# A_INPUT.net
KiCad netlist of a schematic drawn in Altium Designer
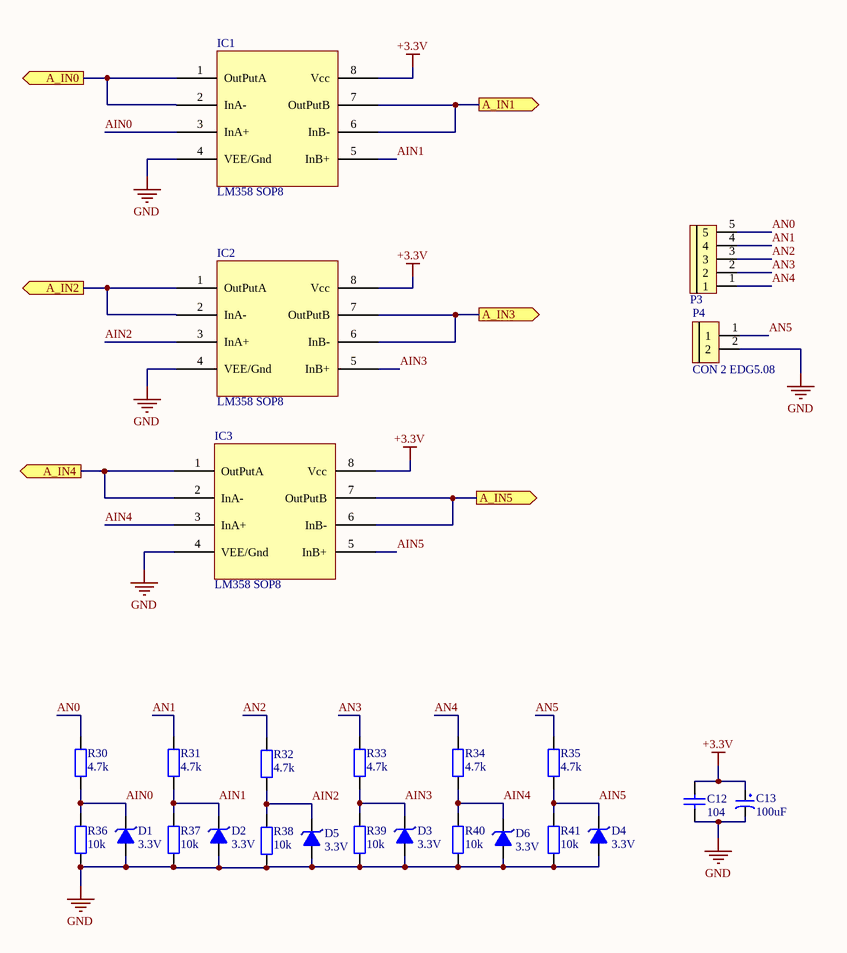
[diagram p0: A_INPUT.SchDoc]

(export (version "E")
  (design (tool "Eeschema 10.0.6"))
  (components
    (comp (ref "C12")
      (value "104")
      (footprint "tu 0805")
      (description "Dán")
      (libsource (lib "Altium_Lib_by_KhueNguyenCreator") (part "Tu 0805 104 50V 10%"))
    )
    (comp (ref "C13")
      (value "100uF")
      (footprint "tu hoa 5mm")
      (description "Cắm")
      (libsource (lib "Altium_Lib_by_KhueNguyenCreator") (part "Tu Hoa 100uF 16V 5x7"))
    )
    (comp (ref "D1")
      (value "3.3V")
      (footprint "DIODE ZENNER SMD SOD80")
      (description "Dán")
      (libsource (lib "Altium_Lib_by_KhueNguyenCreator") (part "Diode Zener 3.3V"))
    )
    (comp (ref "D2")
      (value "3.3V")
      (footprint "DIODE ZENNER SMD SOD80")
      (description "Dán")
      (libsource (lib "Altium_Lib_by_KhueNguyenCreator") (part "Diode Zener 3.3V"))
    )
    (comp (ref "D3")
      (value "3.3V")
      (footprint "DIODE ZENNER SMD SOD80")
      (description "Dán")
      (libsource (lib "Altium_Lib_by_KhueNguyenCreator") (part "Diode Zener 3.3V"))
    )
    (comp (ref "D4")
      (value "3.3V")
      (footprint "DIODE ZENNER SMD SOD80")
      (description "Dán")
      (libsource (lib "Altium_Lib_by_KhueNguyenCreator") (part "Diode Zener 3.3V"))
    )
    (comp (ref "D5")
      (value "3.3V")
      (footprint "DIODE ZENNER SMD SOD80")
      (description "Dán")
      (libsource (lib "Altium_Lib_by_KhueNguyenCreator") (part "Diode Zener 3.3V"))
    )
    (comp (ref "D6")
      (value "3.3V")
      (footprint "DIODE ZENNER SMD SOD80")
      (description "Dán")
      (libsource (lib "Altium_Lib_by_KhueNguyenCreator") (part "Diode Zener 3.3V"))
    )
    (comp (ref "IC1")
      (value "LM358 SOP8")
      (footprint "SOP 8")
      (description "Dán")
      (libsource (lib "Altium_Lib_by_KhueNguyenCreator") (part "LM358 SOP8"))
    )
    (comp (ref "IC2")
      (value "LM358 SOP8")
      (footprint "SOP 8")
      (description "Dán")
      (libsource (lib "Altium_Lib_by_KhueNguyenCreator") (part "LM358 SOP8"))
    )
    (comp (ref "IC3")
      (value "LM358 SOP8")
      (footprint "SOP 8")
      (description "Dán")
      (libsource (lib "Altium_Lib_by_KhueNguyenCreator") (part "LM358 SOP8"))
    )
    (comp (ref "P3")
      (value "CON 5 EDG5.08")
      (footprint "CON 5 5EDG5.08")
      (description "Cắm")
      (libsource (lib "Altium_Lib_by_KhueNguyenCreator") (part "CON 5 EDG5.08"))
    )
    (comp (ref "P4")
      (value "CON 2 EDG5.08")
      (footprint "CON 2 2EDG5.08")
      (description "Cắm")
      (libsource (lib "Altium_Lib_by_KhueNguyenCreator") (part "CON 2 EDG5.08"))
    )
    (comp (ref "R30")
      (value "4.7k")
      (footprint "tro smd 0805")
      (description "Dán")
      (libsource (lib "Altium_Lib_by_KhueNguyenCreator") (part "Tro 0805 1% 5.1k"))
    )
    (comp (ref "R31")
      (value "4.7k")
      (footprint "tro smd 0805")
      (description "Dán")
      (libsource (lib "Altium_Lib_by_KhueNguyenCreator") (part "Tro 0805 1% 5.1k"))
    )
    (comp (ref "R32")
      (value "4.7k")
      (footprint "tro smd 0805")
      (description "Dán")
      (libsource (lib "Altium_Lib_by_KhueNguyenCreator") (part "Tro 0805 1% 5.1k"))
    )
    (comp (ref "R33")
      (value "4.7k")
      (footprint "tro smd 0805")
      (description "Dán")
      (libsource (lib "Altium_Lib_by_KhueNguyenCreator") (part "Tro 0805 1% 5.1k"))
    )
    (comp (ref "R34")
      (value "4.7k")
      (footprint "tro smd 0805")
      (description "Dán")
      (libsource (lib "Altium_Lib_by_KhueNguyenCreator") (part "Tro 0805 1% 5.1k"))
    )
    (comp (ref "R35")
      (value "4.7k")
      (footprint "tro smd 0805")
      (description "Dán")
      (libsource (lib "Altium_Lib_by_KhueNguyenCreator") (part "Tro 0805 1% 5.1k"))
    )
    (comp (ref "R36")
      (value "10k")
      (footprint "tro smd 0805")
      (description "Dán")
      (libsource (lib "Altium_Lib_by_KhueNguyenCreator") (part "Tro 0805 1% 10k"))
    )
    (comp (ref "R37")
      (value "10k")
      (footprint "tro smd 0805")
      (description "Dán")
      (libsource (lib "Altium_Lib_by_KhueNguyenCreator") (part "Tro 0805 1% 10k"))
    )
    (comp (ref "R38")
      (value "10k")
      (footprint "tro smd 0805")
      (description "Dán")
      (libsource (lib "Altium_Lib_by_KhueNguyenCreator") (part "Tro 0805 1% 10k"))
    )
    (comp (ref "R39")
      (value "10k")
      (footprint "tro smd 0805")
      (description "Dán")
      (libsource (lib "Altium_Lib_by_KhueNguyenCreator") (part "Tro 0805 1% 10k"))
    )
    (comp (ref "R40")
      (value "10k")
      (footprint "tro smd 0805")
      (description "Dán")
      (libsource (lib "Altium_Lib_by_KhueNguyenCreator") (part "Tro 0805 1% 10k"))
    )
    (comp (ref "R41")
      (value "10k")
      (footprint "tro smd 0805")
      (description "Dán")
      (libsource (lib "Altium_Lib_by_KhueNguyenCreator") (part "Tro 0805 1% 10k"))
    )
  )
  (nets
    (net (code "1") (name "+3.3V") (class "Default")
      (node (ref "C12") (pin "1") (pinfunction "1_1") (pintype "passive"))
      (node (ref "C13") (pin "1") (pinfunction "1_1") (pintype "passive"))
      (node (ref "IC1") (pin "8") (pinfunction "Vcc_8") (pintype "passive"))
      (node (ref "IC2") (pin "8") (pinfunction "Vcc_8") (pintype "passive"))
      (node (ref "IC3") (pin "8") (pinfunction "Vcc_8") (pintype "passive"))
    )
    (net (code "2") (name "/AIN0") (class "Default")
      (node (ref "D1") (pin "2") (pinfunction "K_2") (pintype "passive"))
      (node (ref "IC1") (pin "3") (pinfunction "InA+_3") (pintype "passive"))
      (node (ref "R30") (pin "1") (pinfunction "1_1") (pintype "passive"))
      (node (ref "R36") (pin "2") (pinfunction "2_2") (pintype "passive"))
    )
    (net (code "3") (name "/AIN1") (class "Default")
      (node (ref "D2") (pin "2") (pinfunction "K_2") (pintype "passive"))
      (node (ref "IC1") (pin "5") (pinfunction "InB+_5") (pintype "passive"))
      (node (ref "R31") (pin "1") (pinfunction "1_1") (pintype "passive"))
      (node (ref "R37") (pin "2") (pinfunction "2_2") (pintype "passive"))
    )
    (net (code "4") (name "/AIN2") (class "Default")
      (node (ref "D5") (pin "2") (pinfunction "K_2") (pintype "passive"))
      (node (ref "IC2") (pin "3") (pinfunction "InA+_3") (pintype "passive"))
      (node (ref "R32") (pin "1") (pinfunction "1_1") (pintype "passive"))
      (node (ref "R38") (pin "2") (pinfunction "2_2") (pintype "passive"))
    )
    (net (code "5") (name "/AIN3") (class "Default")
      (node (ref "D3") (pin "2") (pinfunction "K_2") (pintype "passive"))
      (node (ref "IC2") (pin "5") (pinfunction "InB+_5") (pintype "passive"))
      (node (ref "R33") (pin "1") (pinfunction "1_1") (pintype "passive"))
      (node (ref "R39") (pin "2") (pinfunction "2_2") (pintype "passive"))
    )
    (net (code "6") (name "/AIN4") (class "Default")
      (node (ref "D6") (pin "2") (pinfunction "K_2") (pintype "passive"))
      (node (ref "IC3") (pin "3") (pinfunction "InA+_3") (pintype "passive"))
      (node (ref "R34") (pin "1") (pinfunction "1_1") (pintype "passive"))
      (node (ref "R40") (pin "2") (pinfunction "2_2") (pintype "passive"))
    )
    (net (code "7") (name "/AIN5") (class "Default")
      (node (ref "D4") (pin "2") (pinfunction "K_2") (pintype "passive"))
      (node (ref "IC3") (pin "5") (pinfunction "InB+_5") (pintype "passive"))
      (node (ref "R35") (pin "1") (pinfunction "1_1") (pintype "passive"))
      (node (ref "R41") (pin "2") (pinfunction "2_2") (pintype "passive"))
    )
    (net (code "8") (name "/AN0") (class "Default")
      (node (ref "P3") (pin "5") (pinfunction "5_5") (pintype "passive"))
      (node (ref "R30") (pin "2") (pinfunction "2_2") (pintype "passive"))
    )
    (net (code "9") (name "/AN1") (class "Default")
      (node (ref "P3") (pin "4") (pinfunction "4_4") (pintype "passive"))
      (node (ref "R31") (pin "2") (pinfunction "2_2") (pintype "passive"))
    )
    (net (code "10") (name "/AN2") (class "Default")
      (node (ref "P3") (pin "3") (pinfunction "3_3") (pintype "passive"))
      (node (ref "R32") (pin "2") (pinfunction "2_2") (pintype "passive"))
    )
    (net (code "11") (name "/AN3") (class "Default")
      (node (ref "P3") (pin "2") (pinfunction "2_2") (pintype "passive"))
      (node (ref "R33") (pin "2") (pinfunction "2_2") (pintype "passive"))
    )
    (net (code "12") (name "/AN4") (class "Default")
      (node (ref "P3") (pin "1") (pinfunction "1_1") (pintype "passive"))
      (node (ref "R34") (pin "2") (pinfunction "2_2") (pintype "passive"))
    )
    (net (code "13") (name "/AN5") (class "Default")
      (node (ref "P4") (pin "1") (pinfunction "1_1") (pintype "passive"))
      (node (ref "R35") (pin "2") (pinfunction "2_2") (pintype "passive"))
    )
    (net (code "15") (name "/A_IN0") (class "Default")
      (node (ref "IC1") (pin "1") (pinfunction "OutPutA_1") (pintype "passive"))
      (node (ref "IC1") (pin "2") (pinfunction "InA-_2") (pintype "passive"))
    )
    (net (code "17") (name "/A_IN1") (class "Default")
      (node (ref "IC1") (pin "6") (pinfunction "InB-_6") (pintype "passive"))
      (node (ref "IC1") (pin "7") (pinfunction "OutPutB_7") (pintype "passive"))
    )
    (net (code "18") (name "/A_IN2") (class "Default")
      (node (ref "IC2") (pin "1") (pinfunction "OutPutA_1") (pintype "passive"))
      (node (ref "IC2") (pin "2") (pinfunction "InA-_2") (pintype "passive"))
    )
    (net (code "19") (name "/A_IN3") (class "Default")
      (node (ref "IC2") (pin "6") (pinfunction "InB-_6") (pintype "passive"))
      (node (ref "IC2") (pin "7") (pinfunction "OutPutB_7") (pintype "passive"))
    )
    (net (code "20") (name "/A_IN4") (class "Default")
      (node (ref "IC3") (pin "1") (pinfunction "OutPutA_1") (pintype "passive"))
      (node (ref "IC3") (pin "2") (pinfunction "InA-_2") (pintype "passive"))
    )
    (net (code "21") (name "/A_IN5") (class "Default")
      (node (ref "IC3") (pin "6") (pinfunction "InB-_6") (pintype "passive"))
      (node (ref "IC3") (pin "7") (pinfunction "OutPutB_7") (pintype "passive"))
    )
    (net (code "22") (name "GND") (class "Default")
      (node (ref "C12") (pin "2") (pinfunction "2_2") (pintype "passive"))
      (node (ref "C13") (pin "2") (pinfunction "2_2") (pintype "passive"))
      (node (ref "D1") (pin "1") (pinfunction "A_1") (pintype "passive"))
      (node (ref "D2") (pin "1") (pinfunction "A_1") (pintype "passive"))
      (node (ref "D3") (pin "1") (pinfunction "A_1") (pintype "passive"))
      (node (ref "D4") (pin "1") (pinfunction "A_1") (pintype "passive"))
      (node (ref "D5") (pin "1") (pinfunction "A_1") (pintype "passive"))
      (node (ref "D6") (pin "1") (pinfunction "A_1") (pintype "passive"))
      (node (ref "IC1") (pin "4") (pinfunction "VEE/Gnd_4") (pintype "passive"))
      (node (ref "IC2") (pin "4") (pinfunction "VEE/Gnd_4") (pintype "passive"))
      (node (ref "IC3") (pin "4") (pinfunction "VEE/Gnd_4") (pintype "passive"))
      (node (ref "P4") (pin "2") (pinfunction "2_2") (pintype "passive"))
      (node (ref "R36") (pin "1") (pinfunction "1_1") (pintype "passive"))
      (node (ref "R37") (pin "1") (pinfunction "1_1") (pintype "passive"))
      (node (ref "R38") (pin "1") (pinfunction "1_1") (pintype "passive"))
      (node (ref "R39") (pin "1") (pinfunction "1_1") (pintype "passive"))
      (node (ref "R40") (pin "1") (pinfunction "1_1") (pintype "passive"))
      (node (ref "R41") (pin "1") (pinfunction "1_1") (pintype "passive"))
    )
  )
)
